# MAX31855_breakout.net
KiCad netlist of a schematic drawn in EAGLE
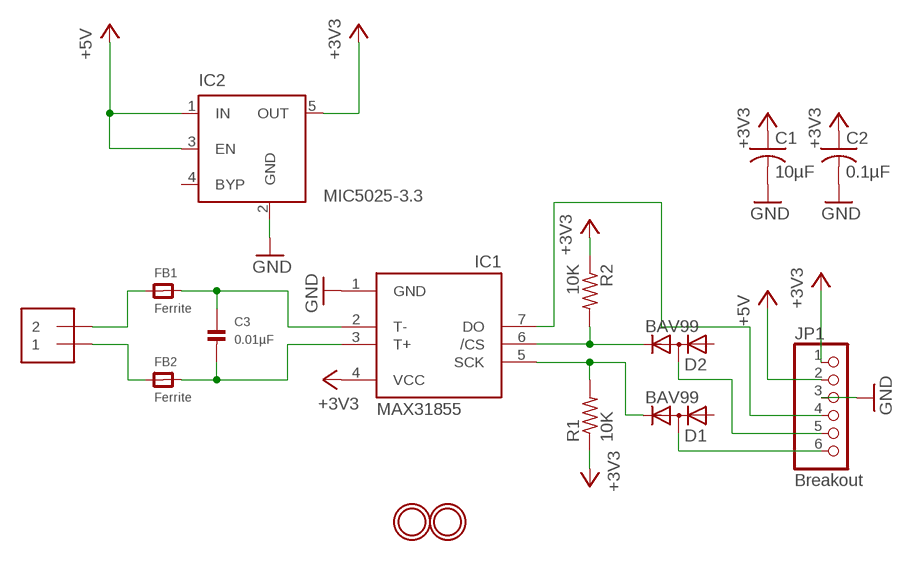
[diagram p0: schematic, sheet 1]

(export (version "E")
  (design (tool "Eeschema 10.0.6"))
  (components
    (comp (ref "C1")
      (value "10µF")
      (footprint "eagle-import:C0805K")
      (libsource (lib "eagle-import") (part "C-USC0805K"))
    )
    (comp (ref "C2")
      (value "0.1µF")
      (footprint "eagle-import:C0805K")
      (libsource (lib "eagle-import") (part "C-USC0805K"))
    )
    (comp (ref "C3")
      (value "0.01µF")
      (footprint "eagle-import:_0805")
      (libsource (lib "eagle-import") (part "CAP_CERAMIC_0805"))
    )
    (comp (ref "D1")
      (value "BAV99")
      (footprint "eagle-import:SOT23")
      (libsource (lib "eagle-import") (part "BAV199"))
    )
    (comp (ref "D2")
      (value "BAV99")
      (footprint "eagle-import:SOT23")
      (libsource (lib "eagle-import") (part "BAV199"))
    )
    (comp (ref "FB1")
      (value "Ferrite")
      (footprint "eagle-import:_0805")
      (libsource (lib "eagle-import") (part "FERRITE_0805"))
    )
    (comp (ref "FB2")
      (value "Ferrite")
      (footprint "eagle-import:_0805")
      (libsource (lib "eagle-import") (part "FERRITE_0805"))
    )
    (comp (ref "IC1")
      (value "MAX31855")
      (footprint "eagle-import:SO08")
      (libsource (lib "eagle-import") (part "MAX6675"))
    )
    (comp (ref "IC2")
      (value "MIC5025-3.3")
      (footprint "eagle-import:SOT23-5")
      (libsource (lib "eagle-import") (part "MIC5219XX"))
    )
    (comp (ref "J1")
      (value "1X2-3.5MM")
      (footprint "eagle-import:1X2-3.5MM")
      (libsource (lib "eagle-import") (part "1X2-3.5MM"))
    )
    (comp (ref "JP1")
      (value "Breakout")
      (footprint "eagle-import:1X06_ROUND_76")
      (libsource (lib "eagle-import") (part "HEADER-1X676MIL"))
    )
    (comp (ref "R1")
      (value "10K")
      (footprint "eagle-import:R0805")
      (libsource (lib "eagle-import") (part "R-US_R0805"))
    )
    (comp (ref "R2")
      (value "10K")
      (footprint "eagle-import:R0805")
      (libsource (lib "eagle-import") (part "R-US_R0805"))
    )
    (comp (ref "U$4")
      (value "MOUNTINGHOLE2.0")
      (footprint "eagle-import:MOUNTINGHOLE_2.0_PLATED")
      (libsource (lib "eagle-import") (part "MOUNTINGHOLE2.0"))
    )
    (comp (ref "U$5")
      (value "MOUNTINGHOLE2.0")
      (footprint "eagle-import:MOUNTINGHOLE_2.0_PLATED")
      (libsource (lib "eagle-import") (part "MOUNTINGHOLE2.0"))
    )
  )
  (nets
    (net (code "1") (name "+3V3") (class "Default")
      (node (ref "C1") (pin "1") (pinfunction "1_1") (pintype "passive"))
      (node (ref "C2") (pin "1") (pinfunction "1_1") (pintype "passive"))
      (node (ref "IC1") (pin "4") (pinfunction "VCC_4") (pintype "power_in"))
      (node (ref "IC2") (pin "5") (pinfunction "OUT_5") (pintype "output"))
      (node (ref "JP1") (pin "1") (pinfunction "1_1") (pintype "passive"))
      (node (ref "R1") (pin "1") (pinfunction "1_1") (pintype "passive"))
      (node (ref "R2") (pin "1") (pinfunction "1_1") (pintype "passive"))
    )
    (net (code "2") (name "+5V") (class "Default")
      (node (ref "IC2") (pin "1") (pinfunction "IN_1") (pintype "input"))
      (node (ref "IC2") (pin "3") (pinfunction "EN_3") (pintype "input"))
      (node (ref "JP1") (pin "2") (pinfunction "2_2") (pintype "passive"))
    )
    (net (code "3") (name "GND") (class "Default")
      (node (ref "C1") (pin "2") (pinfunction "2_2") (pintype "passive"))
      (node (ref "C2") (pin "2") (pinfunction "2_2") (pintype "passive"))
      (node (ref "IC1") (pin "1") (pinfunction "GND_1") (pintype "power_in"))
      (node (ref "IC2") (pin "2") (pinfunction "GND_2") (pintype "power_in"))
      (node (ref "JP1") (pin "3") (pinfunction "3_3") (pintype "passive"))
    )
    (net (code "4") (name "Net-(C3-P$1)") (class "Default")
      (node (ref "C3") (pin "1") (pinfunction "P$1_1") (pintype "passive"))
      (node (ref "FB1") (pin "2") (pinfunction "P$2_2") (pintype "passive"))
      (node (ref "IC1") (pin "2") (pinfunction "T-_2") (pintype "input"))
    )
    (net (code "5") (name "Net-(C3-P$2)") (class "Default")
      (node (ref "C3") (pin "2") (pinfunction "P$2_2") (pintype "passive"))
      (node (ref "FB2") (pin "2") (pinfunction "P$2_2") (pintype "passive"))
      (node (ref "IC1") (pin "3") (pinfunction "T+_3") (pintype "input"))
    )
    (net (code "6") (name "Net-(D1-AC)") (class "Default")
      (node (ref "D1") (pin "3") (pinfunction "AC_3") (pintype "passive"))
      (node (ref "JP1") (pin "6") (pinfunction "6_6") (pintype "passive"))
    )
    (net (code "7") (name "Net-(D1-C)") (class "Default")
      (node (ref "D1") (pin "2") (pinfunction "C_2") (pintype "passive"))
      (node (ref "IC1") (pin "5") (pinfunction "SCK_5") (pintype "input"))
      (node (ref "R1") (pin "2") (pinfunction "2_2") (pintype "passive"))
    )
    (net (code "8") (name "Net-(D2-AC)") (class "Default")
      (node (ref "D2") (pin "3") (pinfunction "AC_3") (pintype "passive"))
      (node (ref "JP1") (pin "5") (pinfunction "5_5") (pintype "passive"))
    )
    (net (code "9") (name "Net-(D2-C)") (class "Default")
      (node (ref "D2") (pin "2") (pinfunction "C_2") (pintype "passive"))
      (node (ref "IC1") (pin "6") (pinfunction "/CS_6") (pintype "input"))
      (node (ref "R2") (pin "2") (pinfunction "2_2") (pintype "passive"))
    )
    (net (code "10") (name "Net-(FB1-P$1)") (class "Default")
      (node (ref "FB1") (pin "1") (pinfunction "P$1_1") (pintype "passive"))
      (node (ref "J1") (pin "2") (pinfunction "2_2") (pintype "passive"))
    )
    (net (code "11") (name "Net-(FB2-P$1)") (class "Default")
      (node (ref "FB2") (pin "1") (pinfunction "P$1_1") (pintype "passive"))
      (node (ref "J1") (pin "1") (pinfunction "1_1") (pintype "passive"))
    )
    (net (code "12") (name "Net-(IC1-DO)") (class "Default")
      (node (ref "IC1") (pin "7") (pinfunction "DO_7") (pintype "output"))
      (node (ref "JP1") (pin "4") (pinfunction "4_4") (pintype "passive"))
    )
    (net (code "13") (name "unconnected-(D1-A-Pad1)") (class "Default")
      (node (ref "D1") (pin "1") (pinfunction "A_1") (pintype "passive"))
    )
    (net (code "14") (name "unconnected-(D2-A-Pad1)") (class "Default")
      (node (ref "D2") (pin "1") (pinfunction "A_1") (pintype "passive"))
    )
    (net (code "15") (name "unconnected-(IC2-BYP-Pad4)") (class "Default")
      (node (ref "IC2") (pin "4") (pinfunction "BYP_4") (pintype "passive"))
    )
  )
)
